# power.net
KiCad netlist of a schematic drawn in Altium Designer
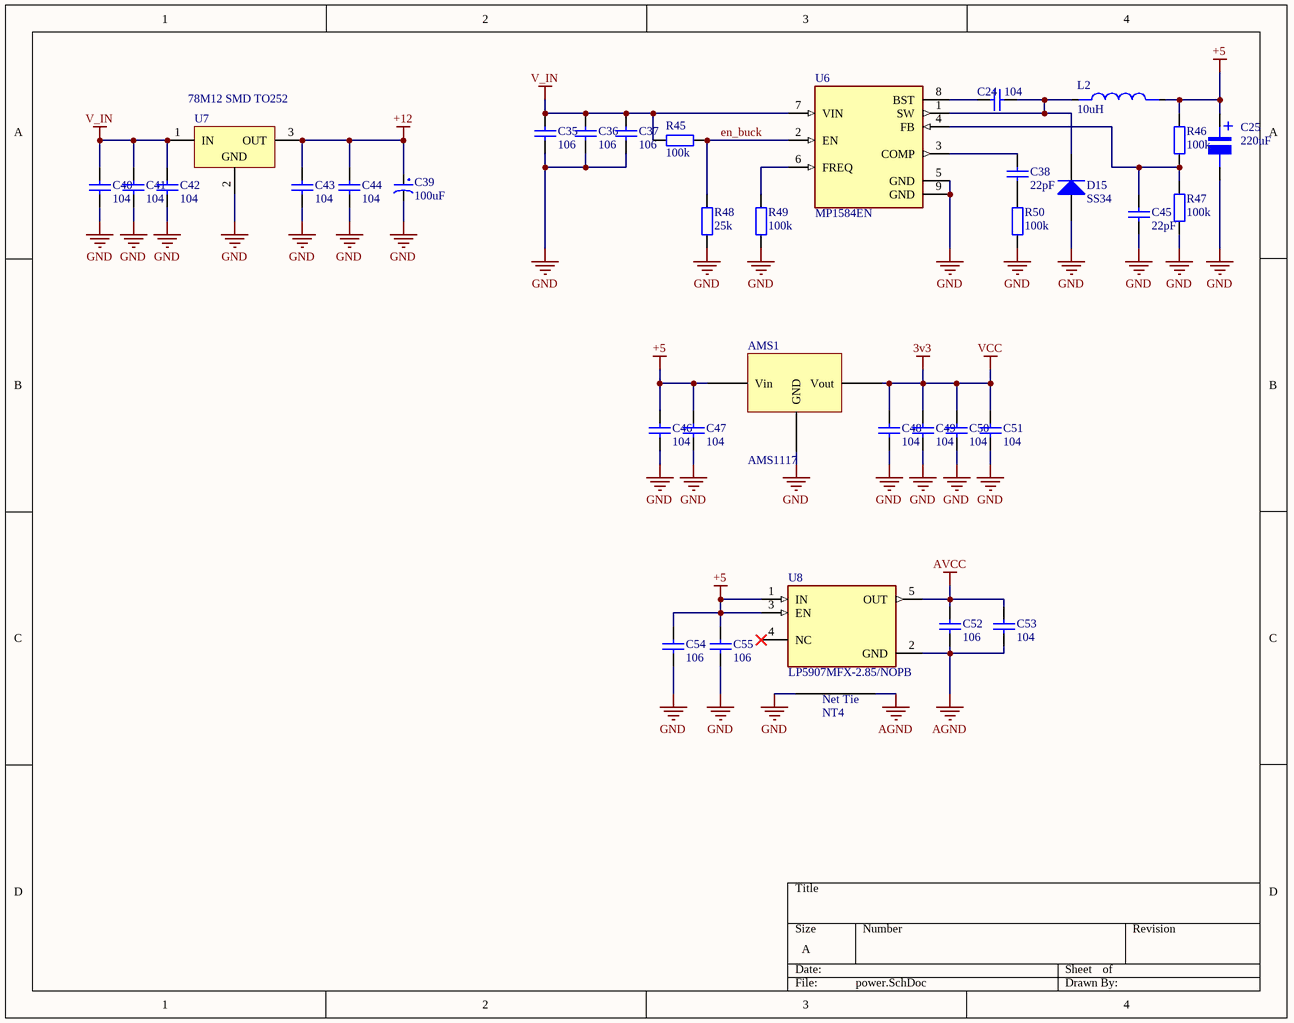
[diagram p0: power.SchDoc]

(export (version "E")
  (design (tool "Eeschema 10.0.6"))
  (components
    (comp (ref "AMS1")
      (value "AMS1117")
      (footprint "TO 252")
      (libsource (lib "Driver4.0_Project_Fix_source_5V") (part "AMS1117"))
    )
    (comp (ref "C24")
      (value "104")
      (footprint "tu 0603")
      (description "Dán")
      (libsource (lib "Altium_Lib_by_KhueNguyenCreator") (part "Tu 0603 104 50V 10%"))
    )
    (comp (ref "C25")
      (value "220uF")
      (footprint "tu nhom 6.3 (d)")
      (description "Dán")
      (libsource (lib "Altium_Lib_by_KhueNguyenCreator") (part "Tu Nhom 220uF 16V"))
    )
    (comp (ref "C35")
      (value "106")
      (footprint "tu 0805")
      (description "Dán")
      (libsource (lib "Altium_Lib_by_KhueNguyenCreator") (part "Tu 0805 106 16V 10%"))
    )
    (comp (ref "C36")
      (value "106")
      (footprint "tu 0805")
      (description "Dán")
      (libsource (lib "Altium_Lib_by_KhueNguyenCreator") (part "Tu 0805 106 16V 10%"))
    )
    (comp (ref "C37")
      (value "106")
      (footprint "tu 0805")
      (description "Dán")
      (libsource (lib "Altium_Lib_by_KhueNguyenCreator") (part "Tu 0805 106 16V 10%"))
    )
    (comp (ref "C38")
      (value "22pF")
      (footprint "tu 0805")
      (description "Dán")
      (libsource (lib "Altium_Lib_by_KhueNguyenCreator") (part "Tu 0805 106 16V 10%"))
    )
    (comp (ref "C39")
      (value "100uF")
      (footprint "tu hoa 8mm")
      (description "Cắm")
      (libsource (lib "Altium_Lib_by_KhueNguyenCreator") (part "Tu Hoa 100uF 35V 8x11"))
    )
    (comp (ref "C40")
      (value "104")
      (footprint "tu 0603")
      (description "Dán")
      (libsource (lib "Altium_Lib_by_KhueNguyenCreator") (part "Tu 0603 101 50V 10%"))
    )
    (comp (ref "C41")
      (value "104")
      (footprint "tu 0603")
      (description "Dán")
      (libsource (lib "Altium_Lib_by_KhueNguyenCreator") (part "Tu 0603 101 50V 10%"))
    )
    (comp (ref "C42")
      (value "104")
      (footprint "tu 0603")
      (description "Dán")
      (libsource (lib "Altium_Lib_by_KhueNguyenCreator") (part "Tu 0603 101 50V 10%"))
    )
    (comp (ref "C43")
      (value "104")
      (footprint "tu 0603")
      (description "Dán")
      (libsource (lib "Altium_Lib_by_KhueNguyenCreator") (part "Tu 0603 101 50V 10%"))
    )
    (comp (ref "C44")
      (value "104")
      (footprint "tu 0603")
      (description "Dán")
      (libsource (lib "Altium_Lib_by_KhueNguyenCreator") (part "Tu 0603 101 50V 10%"))
    )
    (comp (ref "C45")
      (value "22pF")
      (footprint "tu 0805")
      (description "Dán")
      (libsource (lib "Altium_Lib_by_KhueNguyenCreator") (part "Tu 0805 106 16V 10%"))
    )
    (comp (ref "C46")
      (value "104")
      (footprint "tu 0603")
      (description "Dán")
      (libsource (lib "Altium_Lib_by_KhueNguyenCreator") (part "Tu 0603 101 50V 10%"))
    )
    (comp (ref "C47")
      (value "104")
      (footprint "tu 0603")
      (description "Dán")
      (libsource (lib "Altium_Lib_by_KhueNguyenCreator") (part "Tu 0603 101 50V 10%"))
    )
    (comp (ref "C48")
      (value "104")
      (footprint "tu 0603")
      (description "Dán")
      (libsource (lib "Altium_Lib_by_KhueNguyenCreator") (part "Tu 0603 101 50V 10%"))
    )
    (comp (ref "C49")
      (value "104")
      (footprint "tu 0603")
      (description "Dán")
      (libsource (lib "Altium_Lib_by_KhueNguyenCreator") (part "Tu 0603 101 50V 10%"))
    )
    (comp (ref "C50")
      (value "104")
      (footprint "tu 0603")
      (description "Dán")
      (libsource (lib "Altium_Lib_by_KhueNguyenCreator") (part "Tu 0603 101 50V 10%"))
    )
    (comp (ref "C51")
      (value "104")
      (footprint "tu 0603")
      (description "Dán")
      (libsource (lib "Altium_Lib_by_KhueNguyenCreator") (part "Tu 0603 101 50V 10%"))
    )
    (comp (ref "C52")
      (value "106")
      (footprint "tu 0603")
      (description "Dán")
      (libsource (lib "Altium_Lib_by_KhueNguyenCreator") (part "Tu 0603 106 16V 20%"))
    )
    (comp (ref "C53")
      (value "104")
      (footprint "tu 0603")
      (description "Dán")
      (libsource (lib "Altium_Lib_by_KhueNguyenCreator") (part "Tu 0603 106 16V 20%"))
    )
    (comp (ref "C54")
      (value "106")
      (footprint "tu 0603")
      (description "Dán")
      (libsource (lib "Altium_Lib_by_KhueNguyenCreator") (part "Tu 0603 106 16V 20%"))
    )
    (comp (ref "C55")
      (value "106")
      (footprint "tu 0603")
      (description "Dán")
      (libsource (lib "Altium_Lib_by_KhueNguyenCreator") (part "Tu 0603 106 16V 20%"))
    )
    (comp (ref "D15")
      (value "SS34")
      (footprint "DIODE SMA")
      (description "Dán")
      (libsource (lib "Altium_Lib_by_KhueNguyenCreator") (part "Diode SS34 ( 1N5822 )"))
    )
    (comp (ref "L2")
      (value "10uH")
      (footprint "CUON CAM SMD 0530")
      (description "SMD 0530")
      (fields (field (name "MP") "FDV0530-H-1R5M=P3"))
      (libsource (lib "Altium_Lib_by_KhueNguyenCreator") (part "Cuon Cam SMD 0530"))
    )
    (comp (ref "NT4") (value "2mm") (footprint "NetTie_20mil") (libsource (lib "EIT_V3") (part "NetTie_2mm")))
    (comp (ref "R45")
      (value "100k")
      (footprint "tro smd 0603")
      (description "Dán")
      (libsource (lib "Altium_Lib_by_KhueNguyenCreator") (part "Tro 0603 1% 0R"))
    )
    (comp (ref "R46")
      (value "100k")
      (footprint "tro smd 0603")
      (description "Dán")
      (libsource (lib "Altium_Lib_by_KhueNguyenCreator") (part "Tro 0603 1% 0R"))
    )
    (comp (ref "R47")
      (value "100k")
      (footprint "tro smd 0603")
      (description "Dán")
      (libsource (lib "Altium_Lib_by_KhueNguyenCreator") (part "Tro 0603 1% 0R"))
    )
    (comp (ref "R48")
      (value "25k")
      (footprint "tro smd 0603")
      (description "Dán")
      (libsource (lib "Altium_Lib_by_KhueNguyenCreator") (part "Tro 0603 1% 0R"))
    )
    (comp (ref "R49")
      (value "100k")
      (footprint "tro smd 0603")
      (description "Dán")
      (libsource (lib "Altium_Lib_by_KhueNguyenCreator") (part "Tro 0603 1% 0R"))
    )
    (comp (ref "R50")
      (value "100k")
      (footprint "tro smd 0603")
      (description "Dán")
      (libsource (lib "Altium_Lib_by_KhueNguyenCreator") (part "Tro 0603 1% 0R"))
    )
    (comp (ref "U6")
      (value "MP1584EN")
      (footprint "SOIC127P600X170-9N")
      (fields (field (name "MF") "Monolithic Power"))
      (libsource (lib "MP1584EN") (part "MP1584EN"))
    )
    (comp (ref "U7")
      (value "78M12 SMD TO252")
      (footprint "TO252")
      (description "Dán")
      (libsource (lib "Altium_Lib_by_KhueNguyenCreator") (part "78M05 SMD TO252"))
    )
    (comp (ref "U8")
      (value "LP5907MFX-2.85/NOPB")
      (footprint "SOT95P280X145-5N")
      (description "250-mA, low-noise, high-PSRR, ultra-low-dropout voltage regulator with low IQ and enable")
      (fields (field (name "MF") "Texas Instruments"))
      (libsource (lib "LP5907MFX-2.85_NOPB") (part "LP5907MFX-2.85/NOPB"))
    )
  )
  (nets
    (net (code "1") (name "+5") (class "Default")
      (node (ref "AMS1") (pin "3") (pinfunction "Vin_3") (pintype "passive"))
      (node (ref "C25") (pin "1") (pinfunction "1_1") (pintype "passive"))
      (node (ref "C46") (pin "1") (pinfunction "1_1") (pintype "passive"))
      (node (ref "C47") (pin "1") (pinfunction "1_1") (pintype "passive"))
      (node (ref "C54") (pin "1") (pinfunction "1_1") (pintype "passive"))
      (node (ref "C55") (pin "1") (pinfunction "1_1") (pintype "passive"))
      (node (ref "L2") (pin "2") (pinfunction "2_2") (pintype "passive"))
      (node (ref "R46") (pin "2") (pinfunction "2_2") (pintype "passive"))
      (node (ref "U8") (pin "1") (pinfunction "IN_1") (pintype "input"))
      (node (ref "U8") (pin "3") (pinfunction "EN_3") (pintype "input"))
    )
    (net (code "2") (name "+12") (class "Default")
      (node (ref "C39") (pin "1") (pinfunction "1_1") (pintype "passive"))
      (node (ref "C43") (pin "1") (pinfunction "1_1") (pintype "passive"))
      (node (ref "C44") (pin "1") (pinfunction "1_1") (pintype "passive"))
      (node (ref "U7") (pin "3") (pinfunction "OUT_3") (pintype "power_in"))
    )
    (net (code "3") (name "/en_buck") (class "Default")
      (node (ref "R45") (pin "1") (pinfunction "1_1") (pintype "passive"))
      (node (ref "R48") (pin "2") (pinfunction "2_2") (pintype "passive"))
      (node (ref "U6") (pin "2") (pinfunction "EN_2") (pintype "input"))
    )
    (net (code "4") (name "3v3") (class "Default")
      (node (ref "AMS1") (pin "2") (pinfunction "Vout_2") (pintype "passive"))
      (node (ref "C48") (pin "1") (pinfunction "1_1") (pintype "passive"))
      (node (ref "C49") (pin "1") (pinfunction "1_1") (pintype "passive"))
      (node (ref "C50") (pin "1") (pinfunction "1_1") (pintype "passive"))
      (node (ref "C51") (pin "1") (pinfunction "1_1") (pintype "passive"))
    )
    (net (code "5") (name "AGND") (class "Default")
      (node (ref "C52") (pin "2") (pinfunction "2_2") (pintype "passive"))
      (node (ref "C53") (pin "2") (pinfunction "2_2") (pintype "passive"))
      (node (ref "NT4") (pin "2") (pintype "passive"))
      (node (ref "U8") (pin "2") (pinfunction "GND_2") (pintype "power_in"))
    )
    (net (code "6") (name "AVCC") (class "Default")
      (node (ref "C52") (pin "1") (pinfunction "1_1") (pintype "passive"))
      (node (ref "C53") (pin "1") (pinfunction "1_1") (pintype "passive"))
      (node (ref "U8") (pin "5") (pinfunction "OUT_5") (pintype "output"))
    )
    (net (code "7") (name "GND") (class "Default")
      (node (ref "AMS1") (pin "1") (pinfunction "GND_1") (pintype "passive"))
      (node (ref "C25") (pin "2") (pinfunction "2_2") (pintype "passive"))
      (node (ref "C35") (pin "2") (pinfunction "2_2") (pintype "passive"))
      (node (ref "C36") (pin "2") (pinfunction "2_2") (pintype "passive"))
      (node (ref "C37") (pin "2") (pinfunction "2_2") (pintype "passive"))
      (node (ref "C39") (pin "2") (pinfunction "2_2") (pintype "passive"))
      (node (ref "C40") (pin "2") (pinfunction "2_2") (pintype "passive"))
      (node (ref "C41") (pin "2") (pinfunction "2_2") (pintype "passive"))
      (node (ref "C42") (pin "2") (pinfunction "2_2") (pintype "passive"))
      (node (ref "C43") (pin "2") (pinfunction "2_2") (pintype "passive"))
      (node (ref "C44") (pin "2") (pinfunction "2_2") (pintype "passive"))
      (node (ref "C45") (pin "2") (pinfunction "2_2") (pintype "passive"))
      (node (ref "C46") (pin "2") (pinfunction "2_2") (pintype "passive"))
      (node (ref "C47") (pin "2") (pinfunction "2_2") (pintype "passive"))
      (node (ref "C48") (pin "2") (pinfunction "2_2") (pintype "passive"))
      (node (ref "C49") (pin "2") (pinfunction "2_2") (pintype "passive"))
      (node (ref "C50") (pin "2") (pinfunction "2_2") (pintype "passive"))
      (node (ref "C51") (pin "2") (pinfunction "2_2") (pintype "passive"))
      (node (ref "C54") (pin "2") (pinfunction "2_2") (pintype "passive"))
      (node (ref "C55") (pin "2") (pinfunction "2_2") (pintype "passive"))
      (node (ref "D15") (pin "1") (pinfunction "A_1") (pintype "passive"))
      (node (ref "NT4") (pin "1") (pintype "passive"))
      (node (ref "R47") (pin "1") (pinfunction "1_1") (pintype "passive"))
      (node (ref "R48") (pin "1") (pinfunction "1_1") (pintype "passive"))
      (node (ref "R49") (pin "1") (pinfunction "1_1") (pintype "passive"))
      (node (ref "R50") (pin "1") (pinfunction "1_1") (pintype "passive"))
      (node (ref "U6") (pin "5") (pinfunction "GND_5") (pintype "power_in"))
      (node (ref "U6") (pin "9") (pinfunction "GND_9") (pintype "power_in"))
      (node (ref "U7") (pin "2") (pinfunction "GND_2") (pintype "power_in"))
    )
    (net (code "8") (name "Net-(C38-Pad2)") (class "Default")
      (node (ref "C38") (pin "2") (pinfunction "2_2") (pintype "passive"))
      (node (ref "R50") (pin "2") (pinfunction "2_2") (pintype "passive"))
    )
    (net (code "9") (name "Net-(D15-K)") (class "Default")
      (node (ref "C24") (pin "1") (pinfunction "1_1") (pintype "passive"))
      (node (ref "D15") (pin "2") (pinfunction "K_2") (pintype "passive"))
      (node (ref "L2") (pin "1") (pinfunction "1_1") (pintype "passive"))
      (node (ref "U6") (pin "1") (pinfunction "SW_1") (pintype "output"))
    )
    (net (code "10") (name "Net-(U6-BST)") (class "Default")
      (node (ref "C24") (pin "2") (pinfunction "2_2") (pintype "passive"))
      (node (ref "U6") (pin "8") (pinfunction "BST_8") (pintype "passive"))
    )
    (net (code "11") (name "Net-(U6-COMP)") (class "Default")
      (node (ref "C38") (pin "1") (pinfunction "1_1") (pintype "passive"))
      (node (ref "U6") (pin "3") (pinfunction "COMP_3") (pintype "output"))
    )
    (net (code "12") (name "Net-(U6-FB)") (class "Default")
      (node (ref "C45") (pin "1") (pinfunction "1_1") (pintype "passive"))
      (node (ref "R46") (pin "1") (pinfunction "1_1") (pintype "passive"))
      (node (ref "R47") (pin "2") (pinfunction "2_2") (pintype "passive"))
      (node (ref "U6") (pin "4") (pinfunction "FB_4") (pintype "input"))
    )
    (net (code "13") (name "Net-(U6-FREQ)") (class "Default")
      (node (ref "R49") (pin "2") (pinfunction "2_2") (pintype "passive"))
      (node (ref "U6") (pin "6") (pinfunction "FREQ_6") (pintype "input"))
    )
    (net (code "14") (name "V_IN") (class "Default")
      (node (ref "C35") (pin "1") (pinfunction "1_1") (pintype "passive"))
      (node (ref "C36") (pin "1") (pinfunction "1_1") (pintype "passive"))
      (node (ref "C37") (pin "1") (pinfunction "1_1") (pintype "passive"))
      (node (ref "C40") (pin "1") (pinfunction "1_1") (pintype "passive"))
      (node (ref "C41") (pin "1") (pinfunction "1_1") (pintype "passive"))
      (node (ref "C42") (pin "1") (pinfunction "1_1") (pintype "passive"))
      (node (ref "R45") (pin "2") (pinfunction "2_2") (pintype "passive"))
      (node (ref "U6") (pin "7") (pinfunction "VIN_7") (pintype "input"))
      (node (ref "U7") (pin "1") (pinfunction "IN_1") (pintype "power_in"))
    )
    (net (code "15") (name "unconnected-(U8-NC-Pad4)") (class "Default")
      (node (ref "U8") (pin "4") (pinfunction "NC_4") (pintype "passive+no_connect"))
    )
  )
)
